# Multivibrator.net
KiCad netlist of a schematic drawn in EasyEDA
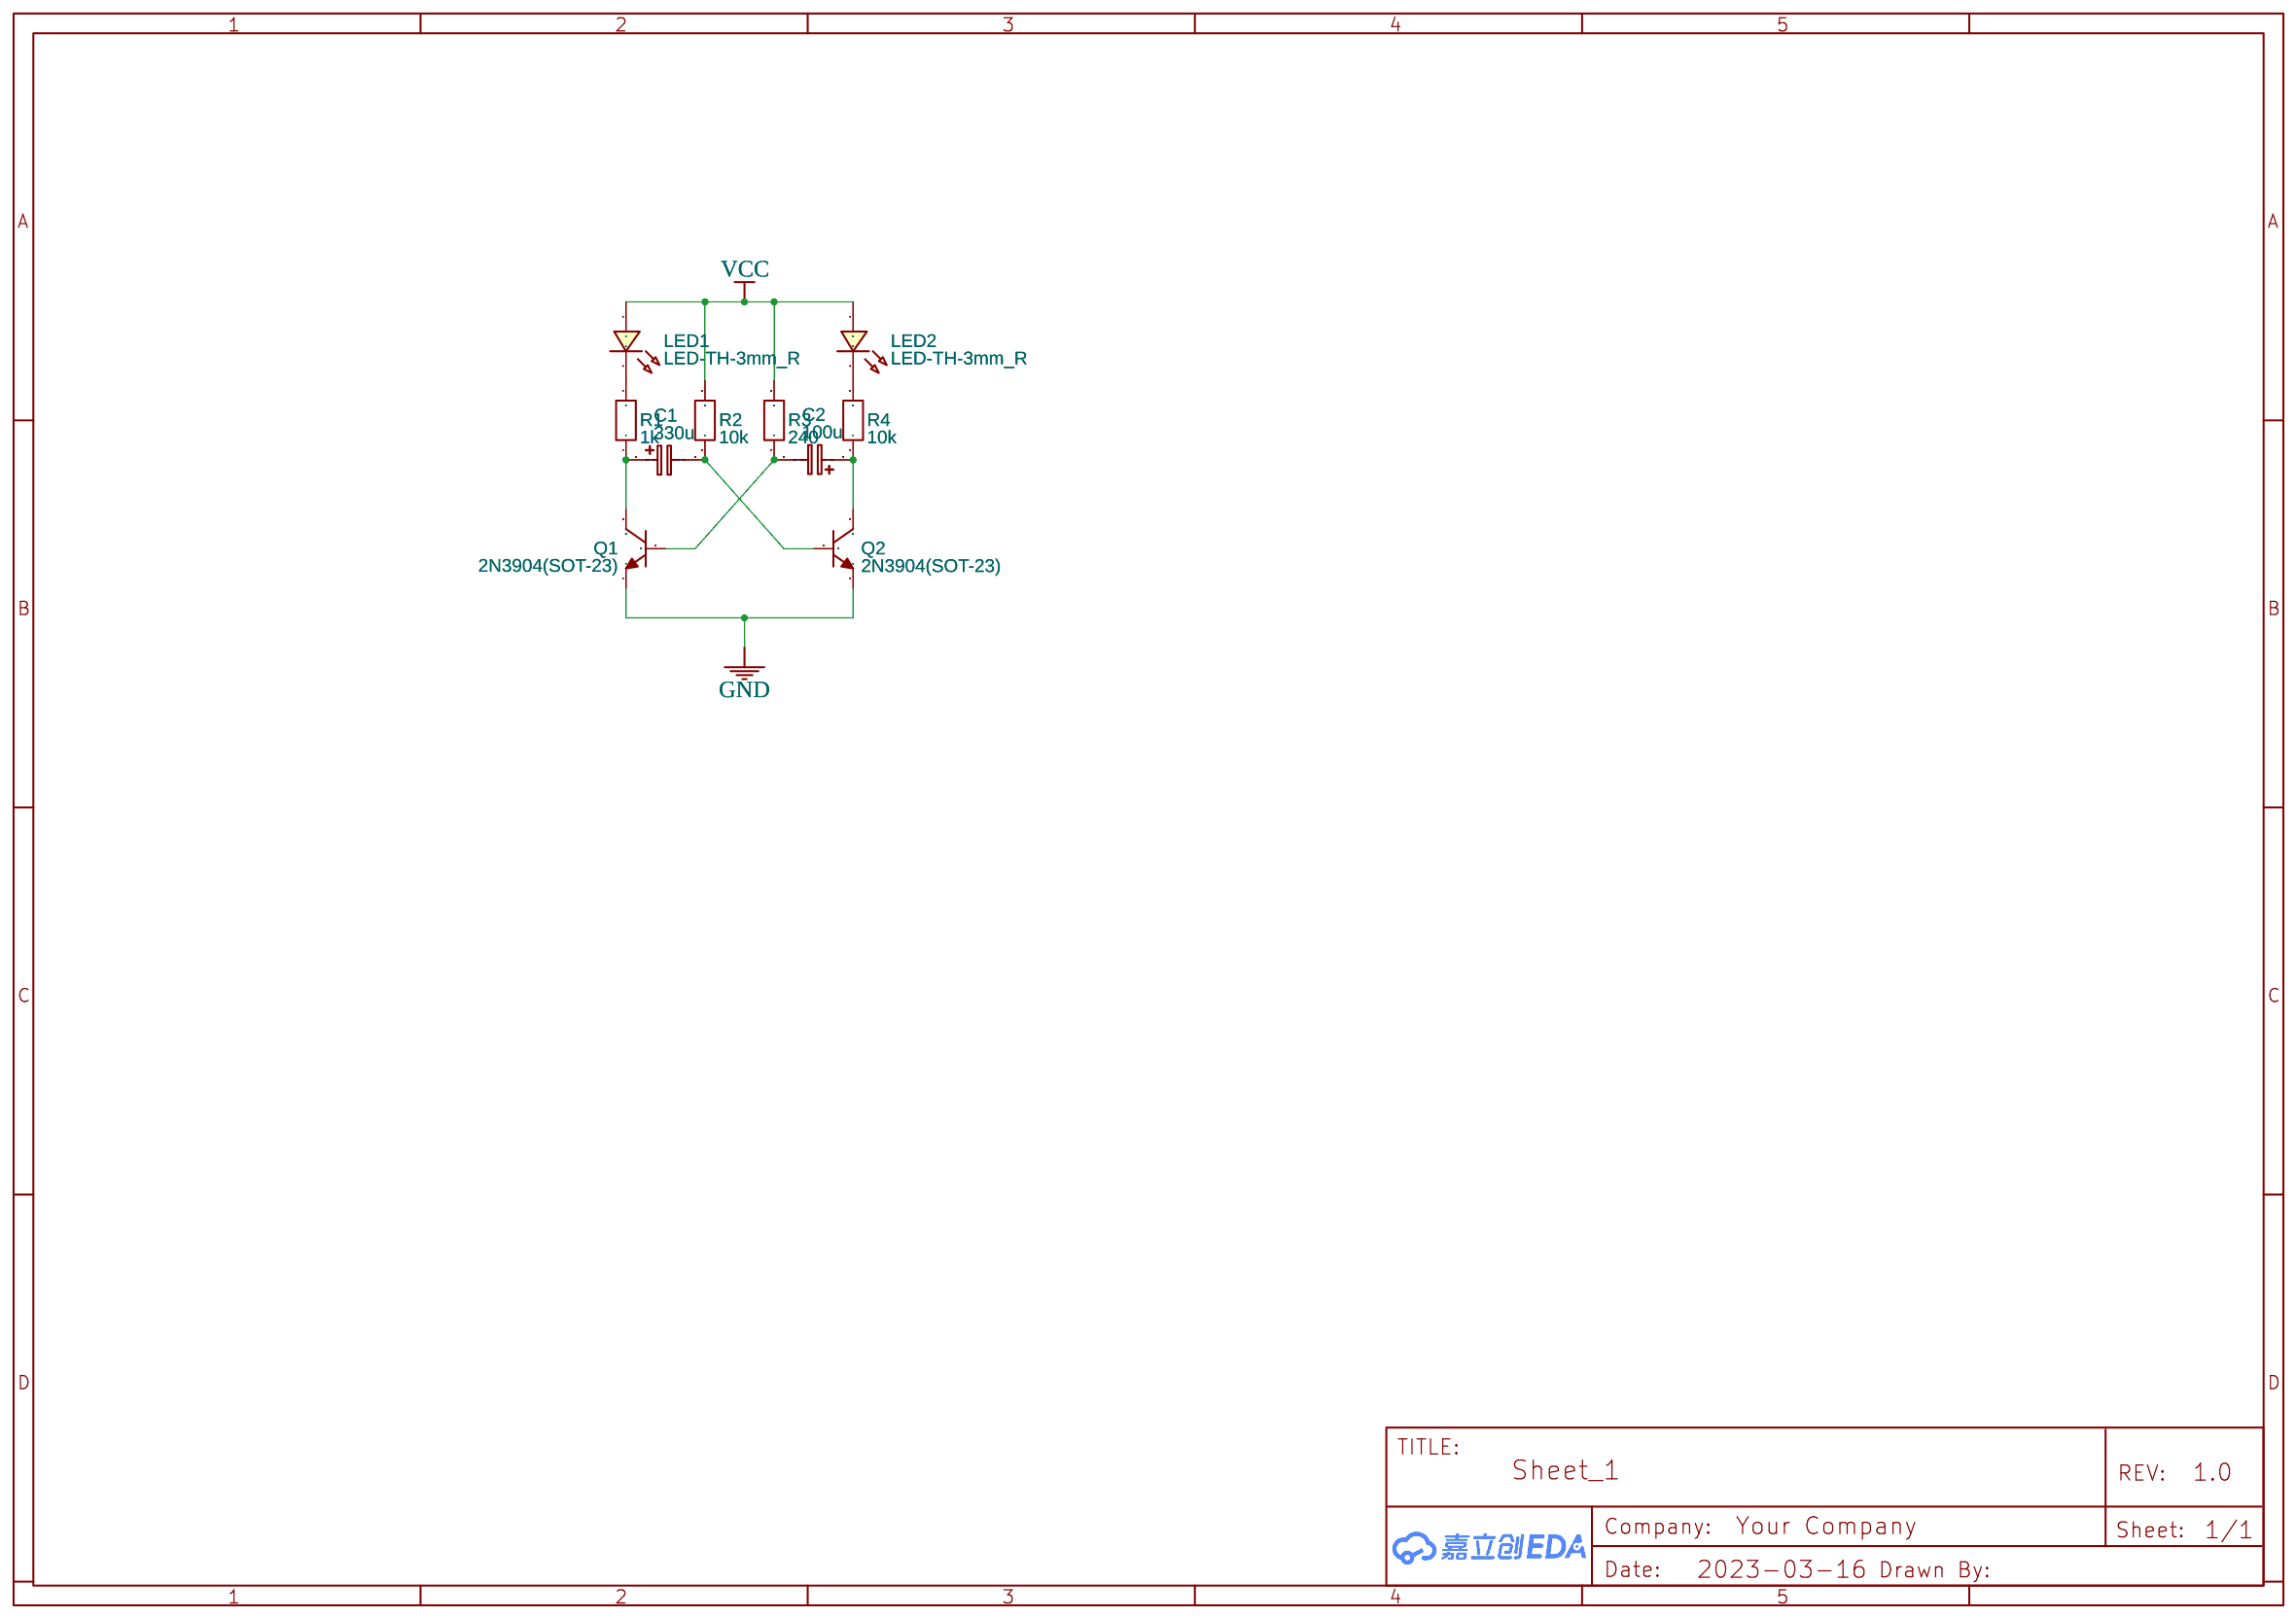
[diagram p0: schematic sheet]

(export (version "E")
  (design (tool "Eeschema 10.0.6"))
  (components
    (comp (ref "C1") (value "330u") (libsource (lib "") (part "CE_TH_D3.0×F1.5_EU_1")))
    (comp (ref "C2") (value "100u") (libsource (lib "") (part "CE_TH_D3.0×F1.5_EU")))
    (comp (ref "LED1")
      (value "LED-TH-3mm_R")
      (fields
        (field (name "BOM_Manufacturer Part") "204-10SDRD/S530-A3-L")
        (field (name "BOM_Supplier Part") "C84774")
      )
      (libsource (lib "") (part "LED-TH-3mm_R"))
    )
    (comp (ref "LED2")
      (value "LED-TH-3mm_R")
      (fields
        (field (name "BOM_Manufacturer Part") "204-10SDRD/S530-A3-L")
        (field (name "BOM_Supplier Part") "C84774")
      )
      (libsource (lib "") (part "LED-TH-3mm_R"))
    )
    (comp (ref "Q1")
      (value "2N3904(SOT-23)")
      (fields
        (field (name "BOM_Manufacturer Part") "2n3904S-RTK/PS")
        (field (name "BOM_Supplier Part") "C18536")
      )
      (libsource (lib "") (part "2N3904(SOT-23)_1"))
    )
    (comp (ref "Q2")
      (value "2N3904(SOT-23)")
      (fields
        (field (name "BOM_Manufacturer Part") "2n3904S-RTK/PS")
        (field (name "BOM_Supplier Part") "C18536")
      )
      (libsource (lib "") (part "2N3904(SOT-23)"))
    )
    (comp (ref "R1") (value "1k") (libsource (lib "") (part "R_AXIAL-0.3_EU")))
    (comp (ref "R2") (value "10k") (libsource (lib "") (part "R_AXIAL-0.3_EU")))
    (comp (ref "R3") (value "240") (libsource (lib "") (part "R_AXIAL-0.3_EU")))
    (comp (ref "R4") (value "10k") (libsource (lib "") (part "R_AXIAL-0.3_EU")))
  )
  (nets
    (net (code "1") (name "GND") (class "Default")
      (node (ref "Q1") (pin "1") (pinfunction "E_1") (pintype "input"))
      (node (ref "Q2") (pin "1") (pinfunction "E_1") (pintype "input"))
    )
    (net (code "2") (name "Net-(LED1-Pad2)") (class "Default")
      (node (ref "LED1") (pin "2") (pinfunction "2_2") (pintype "unspecified"))
      (node (ref "R1") (pin "2") (pinfunction "2_2") (pintype "unspecified"))
    )
    (net (code "3") (name "Net-(LED2-Pad2)") (class "Default")
      (node (ref "LED2") (pin "2") (pinfunction "2_2") (pintype "unspecified"))
      (node (ref "R4") (pin "2") (pinfunction "2_2") (pintype "unspecified"))
    )
    (net (code "4") (name "Net-(Q1-B)") (class "Default")
      (node (ref "C2") (pin "2") (pinfunction "2_2") (pintype "unspecified"))
      (node (ref "Q1") (pin "2") (pinfunction "B_2") (pintype "input"))
      (node (ref "R3") (pin "1") (pinfunction "1_1") (pintype "unspecified"))
    )
    (net (code "5") (name "Net-(Q1-C)") (class "Default")
      (node (ref "C1") (pin "1") (pinfunction "1_1") (pintype "unspecified"))
      (node (ref "Q1") (pin "3") (pinfunction "C_3") (pintype "input"))
      (node (ref "R1") (pin "1") (pinfunction "1_1") (pintype "unspecified"))
    )
    (net (code "6") (name "Net-(Q2-B)") (class "Default")
      (node (ref "C1") (pin "2") (pinfunction "2_2") (pintype "unspecified"))
      (node (ref "Q2") (pin "2") (pinfunction "B_2") (pintype "input"))
      (node (ref "R2") (pin "1") (pinfunction "1_1") (pintype "unspecified"))
    )
    (net (code "7") (name "Net-(Q2-C)") (class "Default")
      (node (ref "C2") (pin "1") (pinfunction "1_1") (pintype "unspecified"))
      (node (ref "Q2") (pin "3") (pinfunction "C_3") (pintype "input"))
      (node (ref "R4") (pin "1") (pinfunction "1_1") (pintype "unspecified"))
    )
    (net (code "8") (name "VCC") (class "Default")
      (node (ref "LED1") (pin "1") (pinfunction "1_1") (pintype "unspecified"))
      (node (ref "LED2") (pin "1") (pinfunction "1_1") (pintype "unspecified"))
      (node (ref "R2") (pin "2") (pinfunction "2_2") (pintype "unspecified"))
      (node (ref "R3") (pin "2") (pinfunction "2_2") (pintype "unspecified"))
    )
  )
)
